# jtag.net
KiCad netlist of a schematic drawn in Altium Designer
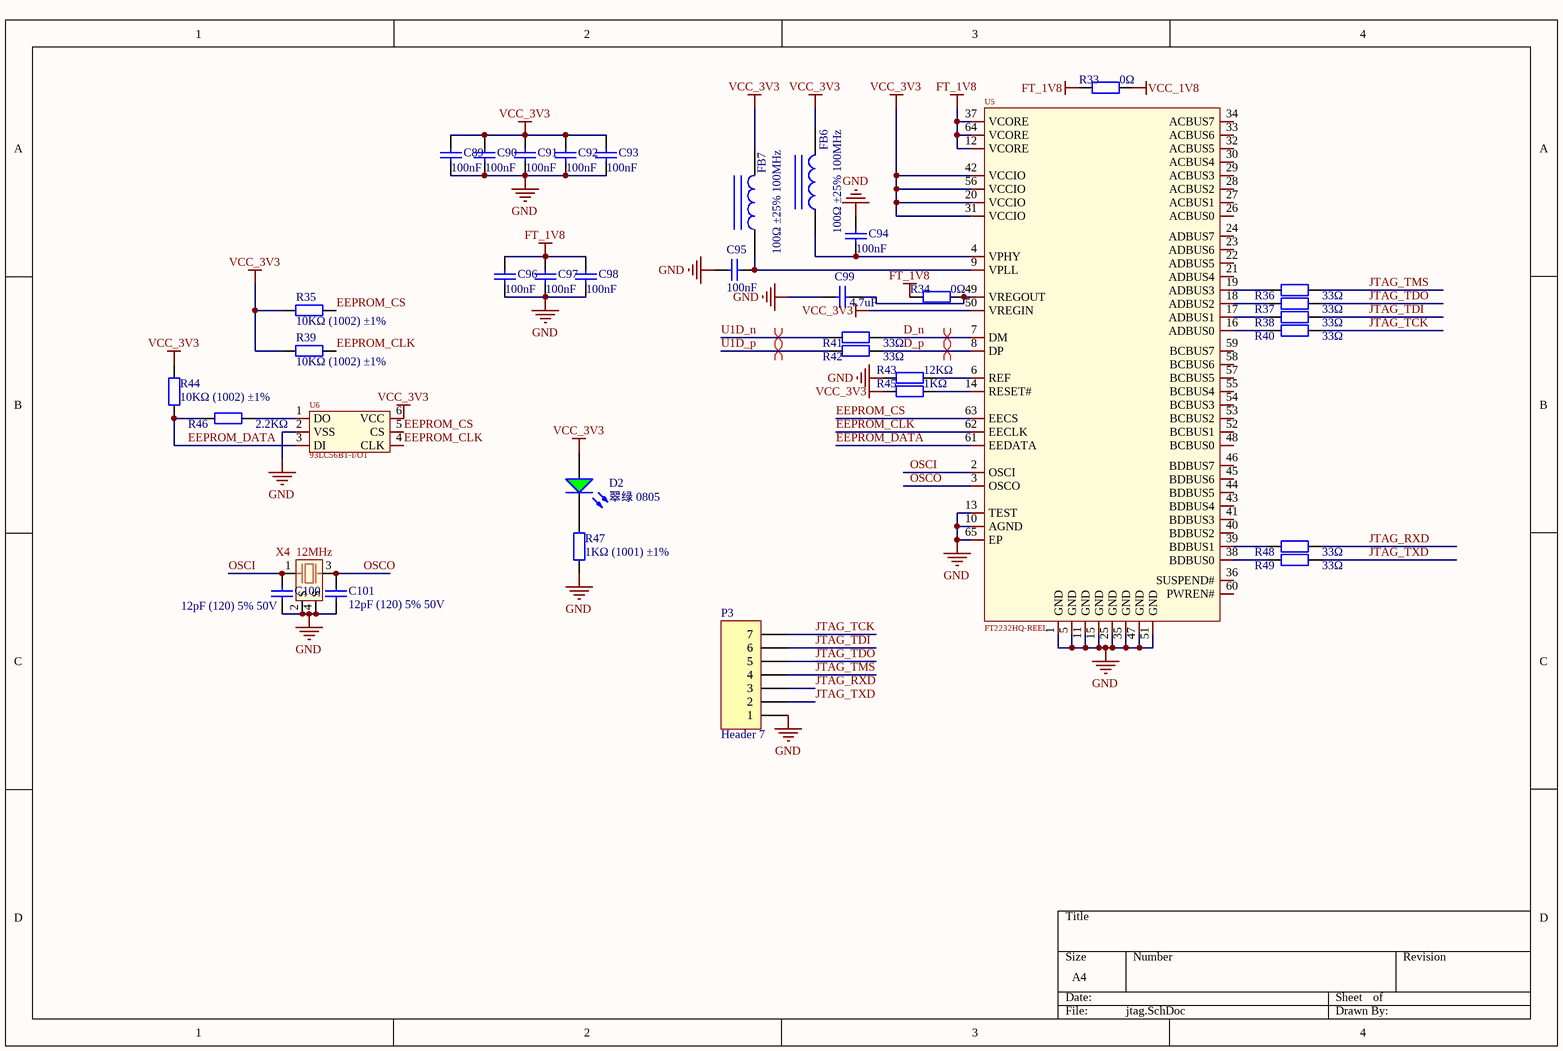
[diagram p0: jtag.SchDoc]

(export (version "E")
  (design (tool "Eeschema 10.0.6"))
  (components
    (comp (ref "C89")
      (value "100nF")
      (footprint "0402_C")
      (description "贴片电容")
      (libsource (lib "Miscellaneous Devices LC") (part "0805 100nF(104) 10% 50V"))
    )
    (comp (ref "C90")
      (value "100nF")
      (footprint "0402_C")
      (description "贴片电容")
      (libsource (lib "Miscellaneous Devices LC") (part "0805 100nF(104) 10% 50V"))
    )
    (comp (ref "C91")
      (value "100nF")
      (footprint "0402_C")
      (description "贴片电容")
      (libsource (lib "Miscellaneous Devices LC") (part "0805 100nF(104) 10% 50V"))
    )
    (comp (ref "C92")
      (value "100nF")
      (footprint "0402_C")
      (description "贴片电容")
      (libsource (lib "Miscellaneous Devices LC") (part "0805 100nF(104) 10% 50V"))
    )
    (comp (ref "C93")
      (value "100nF")
      (footprint "0402_C")
      (description "贴片电容")
      (libsource (lib "Miscellaneous Devices LC") (part "0805 100nF(104) 10% 50V"))
    )
    (comp (ref "C94")
      (value "100nF")
      (footprint "0402_C")
      (description "贴片电容")
      (libsource (lib "Miscellaneous Devices LC") (part "0805 100nF(104) 10% 50V"))
    )
    (comp (ref "C95")
      (value "100nF")
      (footprint "0402_C")
      (description "贴片电容")
      (libsource (lib "Miscellaneous Devices LC") (part "0805 100nF(104) 10% 50V"))
    )
    (comp (ref "C96")
      (value "100nF")
      (footprint "0402_C")
      (description "贴片电容")
      (libsource (lib "Miscellaneous Devices LC") (part "0805 100nF(104) 10% 50V"))
    )
    (comp (ref "C97")
      (value "100nF")
      (footprint "0402_C")
      (description "贴片电容")
      (libsource (lib "Miscellaneous Devices LC") (part "0805 100nF(104) 10% 50V"))
    )
    (comp (ref "C98")
      (value "100nF")
      (footprint "0402_C")
      (description "贴片电容")
      (libsource (lib "Miscellaneous Devices LC") (part "0805 100nF(104) 10% 50V"))
    )
    (comp (ref "C99")
      (value "4.7uF")
      (footprint "0402_C")
      (description "贴片电容")
      (libsource (lib "Miscellaneous Devices LC") (part "0805 4.7uF (475) 10% 25V"))
    )
    (comp (ref "C100")
      (value "12pF (120) 5% 50V")
      (footprint "0402_C")
      (description "贴片电容")
      (libsource (lib "Miscellaneous Devices LC") (part "0805 12pF (120) 5% 50V"))
    )
    (comp (ref "C101")
      (value "12pF (120) 5% 50V")
      (footprint "0402_C")
      (description "贴片电容")
      (libsource (lib "Miscellaneous Devices LC") (part "0805 12pF (120) 5% 50V"))
    )
    (comp (ref "D2")
      (value "翠绿 0805")
      (footprint "0805_LED_S1")
      (description "发光二极管")
      (libsource (lib "Miscellaneous Devices LC") (part "0805 翠绿"))
    )
    (comp (ref "FB6")
      (value "100Ω ±25% 100MHz")
      (footprint "0805_L")
      (description "贴片磁珠")
      (libsource (lib "Miscellaneous Devices LC") (part "0805 100Ω 25% 100MHz"))
    )
    (comp (ref "FB7")
      (value "100Ω ±25% 100MHz")
      (footprint "0805_L")
      (description "贴片磁珠")
      (libsource (lib "Miscellaneous Devices LC") (part "0805 100Ω 25% 100MHz"))
    )
    (comp (ref "P3")
      (value "Header 7")
      (footprint "HDR1X7")
      (description "Header, 7-Pin")
      (fields (field (name "PUBLISHER") "Altium Limited"))
      (libsource (lib "Miscellaneous Connectors") (part "Header 7"))
    )
    (comp (ref "R33")
      (value "0Ω")
      (footprint "0402_R")
      (description "贴片电阻")
      (libsource (lib "Miscellaneous Devices LC") (part "0402 0Ω (0R0) 1%"))
    )
    (comp (ref "R34")
      (value "0Ω")
      (footprint "0402_R")
      (description "贴片电阻")
      (libsource (lib "Miscellaneous Devices LC") (part "0402 0Ω (0R0) 1%"))
    )
    (comp (ref "R35")
      (value "10KΩ (1002) ±1%")
      (footprint "0402_R")
      (description "贴片电阻")
      (libsource (lib "") (part "0805 10KΩ (1002) 1%_1"))
    )
    (comp (ref "R36")
      (value "33Ω")
      (footprint "0402")
      (description "贴片电阻")
      (libsource (lib "Miscellaneous Devices LC") (part "0805 33Ω (33R0) 1%"))
    )
    (comp (ref "R37")
      (value "33Ω")
      (footprint "0402")
      (description "贴片电阻")
      (libsource (lib "Miscellaneous Devices LC") (part "0805 33Ω (33R0) 1%"))
    )
    (comp (ref "R38")
      (value "33Ω")
      (footprint "0402")
      (description "贴片电阻")
      (libsource (lib "Miscellaneous Devices LC") (part "0805 33Ω (33R0) 1%"))
    )
    (comp (ref "R39")
      (value "10KΩ (1002) ±1%")
      (footprint "0402_R")
      (description "贴片电阻")
      (libsource (lib "") (part "0805 10KΩ (1002) 1%_1"))
    )
    (comp (ref "R40")
      (value "33Ω")
      (footprint "0402")
      (description "贴片电阻")
      (libsource (lib "Miscellaneous Devices LC") (part "0805 33Ω (33R0) 1%"))
    )
    (comp (ref "R41")
      (value "33Ω")
      (footprint "0402_R")
      (description "贴片电阻")
      (libsource (lib "Miscellaneous Devices LC") (part "0805 33Ω (33R0) 1%"))
    )
    (comp (ref "R42")
      (value "33Ω")
      (footprint "0402_R")
      (description "贴片电阻")
      (libsource (lib "Miscellaneous Devices LC") (part "0805 33Ω (33R0) 1%"))
    )
    (comp (ref "R43")
      (value "12KΩ")
      (footprint "0402_R")
      (description "贴片电阻")
      (libsource (lib "Miscellaneous Devices LC") (part "0805 12KΩ (1202) 1%"))
    )
    (comp (ref "R44")
      (value "10KΩ (1002) ±1%")
      (footprint "0402_R")
      (description "贴片电阻")
      (libsource (lib "Miscellaneous Devices LC") (part "0805 10KΩ (1002) 1%"))
    )
    (comp (ref "R45")
      (value "1KΩ")
      (footprint "0402_R")
      (description "贴片电阻")
      (libsource (lib "Miscellaneous Devices LC") (part "0805 1KΩ (1001) 1%"))
    )
    (comp (ref "R46")
      (value "2.2KΩ")
      (footprint "0402_R")
      (description "贴片电阻")
      (libsource (lib "Miscellaneous Devices LC") (part "0805 2.2KΩ (2201) 1%"))
    )
    (comp (ref "R47")
      (value "1KΩ (1001) ±1%")
      (footprint "0805_R")
      (description "贴片电阻")
      (libsource (lib "") (part "0805 1KΩ (1001) 1%_1"))
    )
    (comp (ref "R48")
      (value "33Ω")
      (footprint "0402")
      (description "贴片电阻")
      (libsource (lib "Miscellaneous Devices LC") (part "0805 33Ω (33R0) 1%"))
    )
    (comp (ref "R49")
      (value "33Ω")
      (footprint "0402")
      (description "贴片电阻")
      (libsource (lib "Miscellaneous Devices LC") (part "0805 33Ω (33R0) 1%"))
    )
    (comp (ref "U5")
      (value "FT2232HQ-REEL")
      (footprint "QFN-64_L9.0-W9.0-P0.50-TL-EP4.3")
      (fields (field (name "MANUFACTURER") "FTDI(飞特帝亚)"))
      (libsource (lib "五向开关") (part "FT2232HQ-REEL"))
    )
    (comp (ref "U6")
      (value "93LC56BT-I/OT")
      (footprint "SOT-23-6_L2.9-W1.6-P0.95-LS2.8-BR")
      (fields (field (name "MANUFACTURER") "MICROCHIP(美国微芯)"))
      (libsource (lib "五向开关") (part "93LC56BT-I/OT"))
    )
    (comp (ref "X4")
      (value "12MHz")
      (footprint "3225")
      (description "4脚贴片无源晶体")
      (fields (field (name "MANUFACTURER") "YJX(雅晶鑫)") (field (name "MANUFACTURER PART") "TAXM8M4RDBCCT2T"))
      (libsource (lib "五向开关") (part "四脚无源晶体"))
    )
  )
  (nets
    (net (code "1") (name "/D_n") (class "Default")
      (node (ref "R41") (pin "2") (pinfunction "2_2") (pintype "passive"))
      (node (ref "U5") (pin "7") (pinfunction "DM_7") (pintype "passive"))
    )
    (net (code "2") (name "/D_p") (class "Default")
      (node (ref "R42") (pin "2") (pinfunction "2_2") (pintype "passive"))
      (node (ref "U5") (pin "8") (pinfunction "DP_8") (pintype "passive"))
    )
    (net (code "3") (name "/EEPROM_CLK") (class "Default")
      (node (ref "R39") (pin "1") (pinfunction "1_1") (pintype "passive"))
      (node (ref "U5") (pin "62") (pinfunction "EECLK_62") (pintype "passive"))
      (node (ref "U6") (pin "4") (pinfunction "CLK_4") (pintype "passive"))
    )
    (net (code "4") (name "/EEPROM_CS") (class "Default")
      (node (ref "R35") (pin "1") (pinfunction "1_1") (pintype "passive"))
      (node (ref "U5") (pin "63") (pinfunction "EECS_63") (pintype "passive"))
      (node (ref "U6") (pin "5") (pinfunction "CS_5") (pintype "passive"))
    )
    (net (code "5") (name "/EEPROM_DATA") (class "Default")
      (node (ref "R44") (pin "1") (pinfunction "1_1") (pintype "passive"))
      (node (ref "R46") (pin "1") (pinfunction "1_1") (pintype "passive"))
      (node (ref "U5") (pin "61") (pinfunction "EEDATA_61") (pintype "passive"))
      (node (ref "U6") (pin "3") (pinfunction "DI_3") (pintype "passive"))
    )
    (net (code "6") (name "/JTAG_RXD") (class "Default")
      (node (ref "P3") (pin "3") (pinfunction "3_3") (pintype "passive"))
      (node (ref "R48") (pin "2") (pinfunction "2_2") (pintype "passive"))
    )
    (net (code "7") (name "/JTAG_TCK") (class "Default")
      (node (ref "P3") (pin "7") (pinfunction "7_7") (pintype "passive"))
      (node (ref "R40") (pin "2") (pinfunction "2_2") (pintype "passive"))
    )
    (net (code "8") (name "/JTAG_TDI") (class "Default")
      (node (ref "P3") (pin "6") (pinfunction "6_6") (pintype "passive"))
      (node (ref "R38") (pin "2") (pinfunction "2_2") (pintype "passive"))
    )
    (net (code "9") (name "/JTAG_TDO") (class "Default")
      (node (ref "P3") (pin "5") (pinfunction "5_5") (pintype "passive"))
      (node (ref "R37") (pin "2") (pinfunction "2_2") (pintype "passive"))
    )
    (net (code "10") (name "/JTAG_TMS") (class "Default")
      (node (ref "P3") (pin "4") (pinfunction "4_4") (pintype "passive"))
      (node (ref "R36") (pin "2") (pinfunction "2_2") (pintype "passive"))
    )
    (net (code "11") (name "/JTAG_TXD") (class "Default")
      (node (ref "P3") (pin "2") (pinfunction "2_2") (pintype "passive"))
      (node (ref "R49") (pin "2") (pinfunction "2_2") (pintype "passive"))
    )
    (net (code "12") (name "/OSCI") (class "Default")
      (node (ref "C100") (pin "2") (pinfunction "2_2") (pintype "passive"))
      (node (ref "U5") (pin "2") (pinfunction "OSCI_2") (pintype "passive"))
      (node (ref "X4") (pin "1") (pintype "passive"))
    )
    (net (code "13") (name "/OSCO") (class "Default")
      (node (ref "C101") (pin "2") (pinfunction "2_2") (pintype "passive"))
      (node (ref "U5") (pin "3") (pinfunction "OSCO_3") (pintype "passive"))
      (node (ref "X4") (pin "3") (pintype "passive"))
    )
    (net (code "14") (name "/U1D_n") (class "Default")
      (node (ref "R41") (pin "1") (pinfunction "1_1") (pintype "passive"))
    )
    (net (code "15") (name "/U1D_p") (class "Default")
      (node (ref "R42") (pin "1") (pinfunction "1_1") (pintype "passive"))
    )
    (net (code "16") (name "FT_1V8") (class "Default")
      (node (ref "C96") (pin "2") (pinfunction "2_2") (pintype "passive"))
      (node (ref "C97") (pin "2") (pinfunction "2_2") (pintype "passive"))
      (node (ref "C98") (pin "2") (pinfunction "2_2") (pintype "passive"))
      (node (ref "R33") (pin "1") (pinfunction "1_1") (pintype "passive"))
      (node (ref "R34") (pin "1") (pinfunction "1_1") (pintype "passive"))
      (node (ref "U5") (pin "12") (pinfunction "VCORE_12") (pintype "passive"))
      (node (ref "U5") (pin "37") (pinfunction "VCORE_37") (pintype "passive"))
      (node (ref "U5") (pin "64") (pinfunction "VCORE_64") (pintype "passive"))
    )
    (net (code "17") (name "GND") (class "Default")
      (node (ref "C100") (pin "1") (pinfunction "1_1") (pintype "passive"))
      (node (ref "C101") (pin "1") (pinfunction "1_1") (pintype "passive"))
      (node (ref "C89") (pin "1") (pinfunction "1_1") (pintype "passive"))
      (node (ref "C90") (pin "1") (pinfunction "1_1") (pintype "passive"))
      (node (ref "C91") (pin "1") (pinfunction "1_1") (pintype "passive"))
      (node (ref "C92") (pin "1") (pinfunction "1_1") (pintype "passive"))
      (node (ref "C93") (pin "1") (pinfunction "1_1") (pintype "passive"))
      (node (ref "C94") (pin "2") (pinfunction "2_2") (pintype "passive"))
      (node (ref "C95") (pin "2") (pinfunction "2_2") (pintype "passive"))
      (node (ref "C96") (pin "1") (pinfunction "1_1") (pintype "passive"))
      (node (ref "C97") (pin "1") (pinfunction "1_1") (pintype "passive"))
      (node (ref "C98") (pin "1") (pinfunction "1_1") (pintype "passive"))
      (node (ref "C99") (pin "1") (pinfunction "1_1") (pintype "passive"))
      (node (ref "P3") (pin "1") (pinfunction "1_1") (pintype "passive"))
      (node (ref "R43") (pin "1") (pinfunction "1_1") (pintype "passive"))
      (node (ref "R47") (pin "1") (pinfunction "1_1") (pintype "passive"))
      (node (ref "U5") (pin "1") (pinfunction "GND_1") (pintype "passive"))
      (node (ref "U5") (pin "10") (pinfunction "AGND_10") (pintype "passive"))
      (node (ref "U5") (pin "11") (pinfunction "GND_11") (pintype "passive"))
      (node (ref "U5") (pin "13") (pinfunction "TEST_13") (pintype "passive"))
      (node (ref "U5") (pin "15") (pinfunction "GND_15") (pintype "passive"))
      (node (ref "U5") (pin "25") (pinfunction "GND_25") (pintype "passive"))
      (node (ref "U5") (pin "35") (pinfunction "GND_35") (pintype "passive"))
      (node (ref "U5") (pin "47") (pinfunction "GND_47") (pintype "passive"))
      (node (ref "U5") (pin "5") (pinfunction "GND_5") (pintype "passive"))
      (node (ref "U5") (pin "51") (pinfunction "GND_51") (pintype "passive"))
      (node (ref "U5") (pin "65") (pinfunction "EP_65") (pintype "passive"))
      (node (ref "U6") (pin "2") (pinfunction "VSS_2") (pintype "passive"))
      (node (ref "X4") (pin "2") (pinfunction "S_2") (pintype "passive"))
      (node (ref "X4") (pin "4") (pinfunction "S_4") (pintype "passive"))
    )
    (net (code "18") (name "Net-(D2-PadK)") (class "Default")
      (node (ref "D2") (pin "K") (pinfunction "K_K") (pintype "passive"))
      (node (ref "R47") (pin "2") (pinfunction "2_2") (pintype "passive"))
    )
    (net (code "19") (name "Net-(U5-ADBUS0)") (class "Default")
      (node (ref "R40") (pin "1") (pinfunction "1_1") (pintype "passive"))
      (node (ref "U5") (pin "16") (pinfunction "ADBUS0_16") (pintype "passive"))
    )
    (net (code "20") (name "Net-(U5-ADBUS1)") (class "Default")
      (node (ref "R38") (pin "1") (pinfunction "1_1") (pintype "passive"))
      (node (ref "U5") (pin "17") (pinfunction "ADBUS1_17") (pintype "passive"))
    )
    (net (code "21") (name "Net-(U5-ADBUS2)") (class "Default")
      (node (ref "R37") (pin "1") (pinfunction "1_1") (pintype "passive"))
      (node (ref "U5") (pin "18") (pinfunction "ADBUS2_18") (pintype "passive"))
    )
    (net (code "22") (name "Net-(U5-ADBUS3)") (class "Default")
      (node (ref "R36") (pin "1") (pinfunction "1_1") (pintype "passive"))
      (node (ref "U5") (pin "19") (pinfunction "ADBUS3_19") (pintype "passive"))
    )
    (net (code "23") (name "Net-(U5-BDBUS0)") (class "Default")
      (node (ref "R49") (pin "1") (pinfunction "1_1") (pintype "passive"))
      (node (ref "U5") (pin "38") (pinfunction "BDBUS0_38") (pintype "passive"))
    )
    (net (code "24") (name "Net-(U5-BDBUS1)") (class "Default")
      (node (ref "R48") (pin "1") (pinfunction "1_1") (pintype "passive"))
      (node (ref "U5") (pin "39") (pinfunction "BDBUS1_39") (pintype "passive"))
    )
    (net (code "25") (name "Net-(U5-REF)") (class "Default")
      (node (ref "R43") (pin "2") (pinfunction "2_2") (pintype "passive"))
      (node (ref "U5") (pin "6") (pinfunction "REF_6") (pintype "passive"))
    )
    (net (code "26") (name "Net-(U5-RESET#)") (class "Default")
      (node (ref "R45") (pin "2") (pinfunction "2_2") (pintype "passive"))
      (node (ref "U5") (pin "14") (pinfunction "RESET#_14") (pintype "passive"))
    )
    (net (code "27") (name "Net-(U5-VPHY)") (class "Default")
      (node (ref "C94") (pin "1") (pinfunction "1_1") (pintype "passive"))
      (node (ref "FB6") (pin "1") (pinfunction "1_1") (pintype "passive"))
      (node (ref "U5") (pin "4") (pinfunction "VPHY_4") (pintype "passive"))
    )
    (net (code "28") (name "Net-(U5-VPLL)") (class "Default")
      (node (ref "C95") (pin "1") (pinfunction "1_1") (pintype "passive"))
      (node (ref "FB7") (pin "1") (pinfunction "1_1") (pintype "passive"))
      (node (ref "U5") (pin "9") (pinfunction "VPLL_9") (pintype "passive"))
    )
    (net (code "29") (name "Net-(U5-VREGOUT)") (class "Default")
      (node (ref "C99") (pin "2") (pinfunction "2_2") (pintype "passive"))
      (node (ref "R34") (pin "2") (pinfunction "2_2") (pintype "passive"))
      (node (ref "U5") (pin "49") (pinfunction "VREGOUT_49") (pintype "passive"))
    )
    (net (code "30") (name "Net-(U6-DO)") (class "Default")
      (node (ref "R46") (pin "2") (pinfunction "2_2") (pintype "passive"))
      (node (ref "U6") (pin "1") (pinfunction "DO_1") (pintype "passive"))
    )
    (net (code "31") (name "VCC_1V8") (class "Default")
      (node (ref "R33") (pin "2") (pinfunction "2_2") (pintype "passive"))
    )
    (net (code "32") (name "VCC_3V3") (class "Default")
      (node (ref "C89") (pin "2") (pinfunction "2_2") (pintype "passive"))
      (node (ref "C90") (pin "2") (pinfunction "2_2") (pintype "passive"))
      (node (ref "C91") (pin "2") (pinfunction "2_2") (pintype "passive"))
      (node (ref "C92") (pin "2") (pinfunction "2_2") (pintype "passive"))
      (node (ref "C93") (pin "2") (pinfunction "2_2") (pintype "passive"))
      (node (ref "D2") (pin "A") (pinfunction "A_A") (pintype "passive"))
      (node (ref "FB6") (pin "2") (pinfunction "2_2") (pintype "passive"))
      (node (ref "FB7") (pin "2") (pinfunction "2_2") (pintype "passive"))
      (node (ref "R35") (pin "2") (pinfunction "2_2") (pintype "passive"))
      (node (ref "R39") (pin "2") (pinfunction "2_2") (pintype "passive"))
      (node (ref "R44") (pin "2") (pinfunction "2_2") (pintype "passive"))
      (node (ref "R45") (pin "1") (pinfunction "1_1") (pintype "passive"))
      (node (ref "U5") (pin "20") (pinfunction "VCCIO_20") (pintype "passive"))
      (node (ref "U5") (pin "31") (pinfunction "VCCIO_31") (pintype "passive"))
      (node (ref "U5") (pin "42") (pinfunction "VCCIO_42") (pintype "passive"))
      (node (ref "U5") (pin "50") (pinfunction "VREGIN_50") (pintype "passive"))
      (node (ref "U5") (pin "56") (pinfunction "VCCIO_56") (pintype "passive"))
      (node (ref "U6") (pin "6") (pinfunction "VCC_6") (pintype "passive"))
    )
    (net (code "33") (name "unconnected-(U5-ACBUS0-Pad26)") (class "Default")
      (node (ref "U5") (pin "26") (pinfunction "ACBUS0_26") (pintype "passive"))
    )
    (net (code "34") (name "unconnected-(U5-ACBUS1-Pad27)") (class "Default")
      (node (ref "U5") (pin "27") (pinfunction "ACBUS1_27") (pintype "passive"))
    )
    (net (code "35") (name "unconnected-(U5-ACBUS2-Pad28)") (class "Default")
      (node (ref "U5") (pin "28") (pinfunction "ACBUS2_28") (pintype "passive"))
    )
    (net (code "36") (name "unconnected-(U5-ACBUS3-Pad29)") (class "Default")
      (node (ref "U5") (pin "29") (pinfunction "ACBUS3_29") (pintype "passive"))
    )
    (net (code "37") (name "unconnected-(U5-ACBUS4-Pad30)") (class "Default")
      (node (ref "U5") (pin "30") (pinfunction "ACBUS4_30") (pintype "passive"))
    )
    (net (code "38") (name "unconnected-(U5-ACBUS5-Pad32)") (class "Default")
      (node (ref "U5") (pin "32") (pinfunction "ACBUS5_32") (pintype "passive"))
    )
    (net (code "39") (name "unconnected-(U5-ACBUS6-Pad33)") (class "Default")
      (node (ref "U5") (pin "33") (pinfunction "ACBUS6_33") (pintype "passive"))
    )
    (net (code "40") (name "unconnected-(U5-ACBUS7-Pad34)") (class "Default")
      (node (ref "U5") (pin "34") (pinfunction "ACBUS7_34") (pintype "passive"))
    )
    (net (code "41") (name "unconnected-(U5-ADBUS4-Pad21)") (class "Default")
      (node (ref "U5") (pin "21") (pinfunction "ADBUS4_21") (pintype "passive"))
    )
    (net (code "42") (name "unconnected-(U5-ADBUS5-Pad22)") (class "Default")
      (node (ref "U5") (pin "22") (pinfunction "ADBUS5_22") (pintype "passive"))
    )
    (net (code "43") (name "unconnected-(U5-ADBUS6-Pad23)") (class "Default")
      (node (ref "U5") (pin "23") (pinfunction "ADBUS6_23") (pintype "passive"))
    )
    (net (code "44") (name "unconnected-(U5-ADBUS7-Pad24)") (class "Default")
      (node (ref "U5") (pin "24") (pinfunction "ADBUS7_24") (pintype "passive"))
    )
    (net (code "45") (name "unconnected-(U5-BCBUS0-Pad48)") (class "Default")
      (node (ref "U5") (pin "48") (pinfunction "BCBUS0_48") (pintype "passive"))
    )
    (net (code "46") (name "unconnected-(U5-BCBUS1-Pad52)") (class "Default")
      (node (ref "U5") (pin "52") (pinfunction "BCBUS1_52") (pintype "passive"))
    )
    (net (code "47") (name "unconnected-(U5-BCBUS2-Pad53)") (class "Default")
      (node (ref "U5") (pin "53") (pinfunction "BCBUS2_53") (pintype "passive"))
    )
    (net (code "48") (name "unconnected-(U5-BCBUS3-Pad54)") (class "Default")
      (node (ref "U5") (pin "54") (pinfunction "BCBUS3_54") (pintype "passive"))
    )
    (net (code "49") (name "unconnected-(U5-BCBUS4-Pad55)") (class "Default")
      (node (ref "U5") (pin "55") (pinfunction "BCBUS4_55") (pintype "passive"))
    )
    (net (code "50") (name "unconnected-(U5-BCBUS5-Pad57)") (class "Default")
      (node (ref "U5") (pin "57") (pinfunction "BCBUS5_57") (pintype "passive"))
    )
    (net (code "51") (name "unconnected-(U5-BCBUS6-Pad58)") (class "Default")
      (node (ref "U5") (pin "58") (pinfunction "BCBUS6_58") (pintype "passive"))
    )
    (net (code "52") (name "unconnected-(U5-BCBUS7-Pad59)") (class "Default")
      (node (ref "U5") (pin "59") (pinfunction "BCBUS7_59") (pintype "passive"))
    )
    (net (code "53") (name "unconnected-(U5-BDBUS2-Pad40)") (class "Default")
      (node (ref "U5") (pin "40") (pinfunction "BDBUS2_40") (pintype "passive"))
    )
    (net (code "54") (name "unconnected-(U5-BDBUS3-Pad41)") (class "Default")
      (node (ref "U5") (pin "41") (pinfunction "BDBUS3_41") (pintype "passive"))
    )
    (net (code "55") (name "unconnected-(U5-BDBUS4-Pad43)") (class "Default")
      (node (ref "U5") (pin "43") (pinfunction "BDBUS4_43") (pintype "passive"))
    )
    (net (code "56") (name "unconnected-(U5-BDBUS5-Pad44)") (class "Default")
      (node (ref "U5") (pin "44") (pinfunction "BDBUS5_44") (pintype "passive"))
    )
    (net (code "57") (name "unconnected-(U5-BDBUS6-Pad45)") (class "Default")
      (node (ref "U5") (pin "45") (pinfunction "BDBUS6_45") (pintype "passive"))
    )
    (net (code "58") (name "unconnected-(U5-BDBUS7-Pad46)") (class "Default")
      (node (ref "U5") (pin "46") (pinfunction "BDBUS7_46") (pintype "passive"))
    )
    (net (code "59") (name "unconnected-(U5-PWREN#-Pad60)") (class "Default")
      (node (ref "U5") (pin "60") (pinfunction "PWREN#_60") (pintype "passive"))
    )
    (net (code "60") (name "unconnected-(U5-SUSPEND#-Pad36)") (class "Default")
      (node (ref "U5") (pin "36") (pinfunction "SUSPEND#_36") (pintype "passive"))
    )
  )
)
